# pic_can_relay.net
KiCad netlist of a schematic drawn in EAGLE
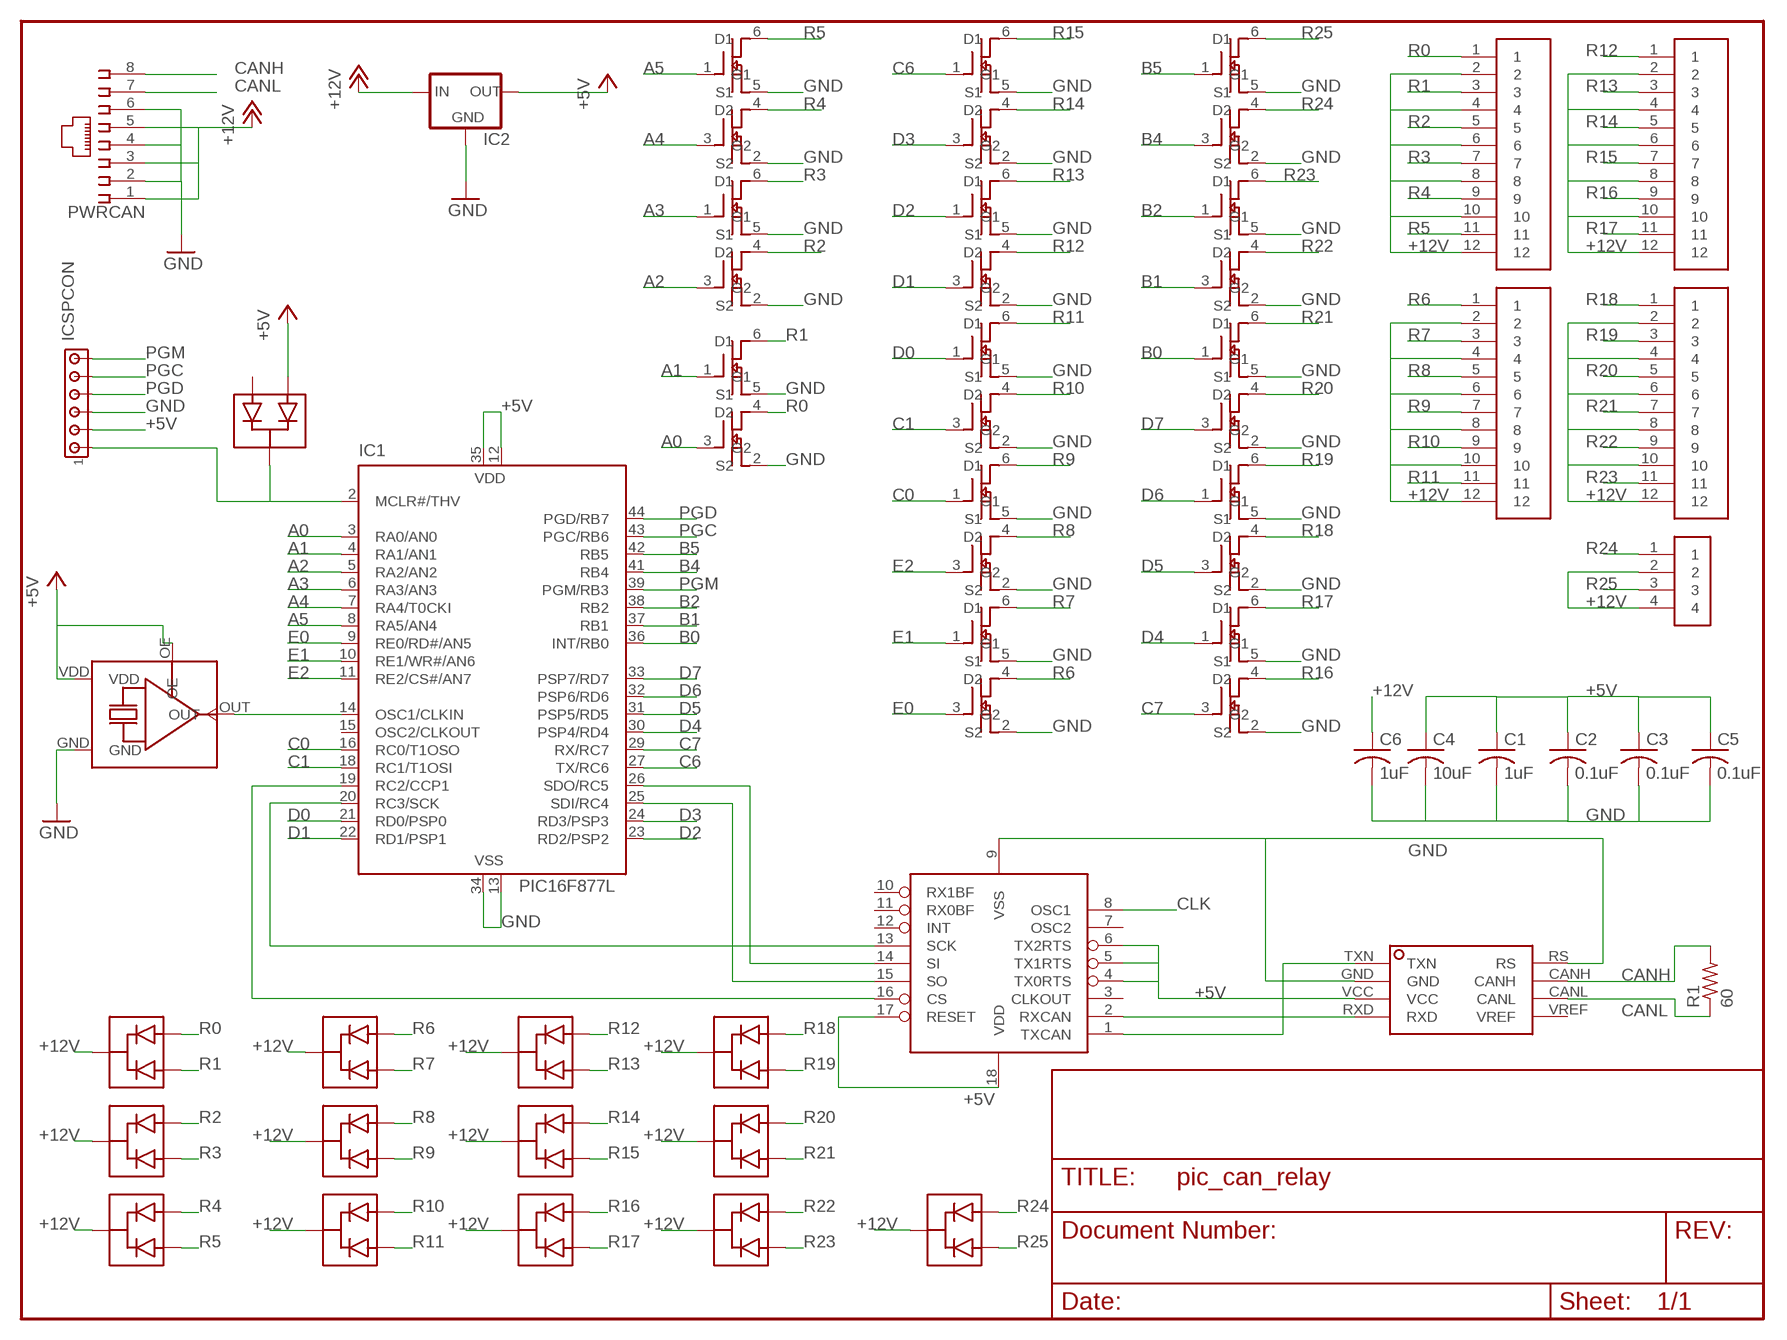
[diagram p0: schematic, sheet 1]

(export (version "E")
  (design (tool "Eeschema 10.0.6"))
  (components
    (comp (ref "C1")
      (value "1uF")
      (footprint "eagle-import:C1206")
      (libsource (lib "eagle-import") (part "C-USC1206"))
    )
    (comp (ref "C2")
      (value "0.1uF")
      (footprint "eagle-import:C0805")
      (libsource (lib "eagle-import") (part "C-USC0805"))
    )
    (comp (ref "C3")
      (value "0.1uF")
      (footprint "eagle-import:C0805")
      (libsource (lib "eagle-import") (part "C-USC0805"))
    )
    (comp (ref "C4")
      (value "10uF")
      (footprint "eagle-import:C1210")
      (libsource (lib "eagle-import") (part "C-USC1210"))
    )
    (comp (ref "C5")
      (value "0.1uF")
      (footprint "eagle-import:C0805")
      (libsource (lib "eagle-import") (part "C-USC0805"))
    )
    (comp (ref "C6")
      (value "1uF")
      (footprint "eagle-import:C1206")
      (libsource (lib "eagle-import") (part "C-USC1206"))
    )
    (comp (ref "D1")
      (value "BAV70_")
      (footprint "eagle-import:SOT-23")
      (libsource (lib "eagle-import") (part "BAV70_"))
    )
    (comp (ref "D2")
      (value "BAV70_")
      (footprint "eagle-import:SOT-23")
      (libsource (lib "eagle-import") (part "BAV70_"))
    )
    (comp (ref "D3")
      (value "BAV70_")
      (footprint "eagle-import:SOT-23")
      (libsource (lib "eagle-import") (part "BAV70_"))
    )
    (comp (ref "D4")
      (value "BAV70_")
      (footprint "eagle-import:SOT-23")
      (libsource (lib "eagle-import") (part "BAV70_"))
    )
    (comp (ref "D5")
      (value "BAV70_")
      (footprint "eagle-import:SOT-23")
      (libsource (lib "eagle-import") (part "BAV70_"))
    )
    (comp (ref "D6")
      (value "BAV70_")
      (footprint "eagle-import:SOT-23")
      (libsource (lib "eagle-import") (part "BAV70_"))
    )
    (comp (ref "D7")
      (value "BAV70_")
      (footprint "eagle-import:SOT-23")
      (libsource (lib "eagle-import") (part "BAV70_"))
    )
    (comp (ref "D8")
      (value "BAV70_")
      (footprint "eagle-import:SOT-23")
      (libsource (lib "eagle-import") (part "BAV70_"))
    )
    (comp (ref "D9")
      (value "BAV70_")
      (footprint "eagle-import:SOT-23")
      (libsource (lib "eagle-import") (part "BAV70_"))
    )
    (comp (ref "D10")
      (value "BAV70_")
      (footprint "eagle-import:SOT-23")
      (libsource (lib "eagle-import") (part "BAV70_"))
    )
    (comp (ref "D11")
      (value "BAV70_")
      (footprint "eagle-import:SOT-23")
      (libsource (lib "eagle-import") (part "BAV70_"))
    )
    (comp (ref "D12")
      (value "BAV70_")
      (footprint "eagle-import:SOT-23")
      (libsource (lib "eagle-import") (part "BAV70_"))
    )
    (comp (ref "D13")
      (value "BAV70_")
      (footprint "eagle-import:SOT-23")
      (libsource (lib "eagle-import") (part "BAV70_"))
    )
    (comp (ref "D14")
      (value "BAV70_")
      (footprint "eagle-import:SOT-23")
      (libsource (lib "eagle-import") (part "BAV70_"))
    )
    (comp (ref "IC1")
      (value "PIC16F877L")
      (footprint "eagle-import:PLCC-44")
      (libsource (lib "eagle-import") (part "PIC16F87L7"))
    )
    (comp (ref "IC2")
      (value "78XXL")
      (footprint "eagle-import:78XXL")
      (libsource (lib "eagle-import") (part "78XXL"))
    )
    (comp (ref "IC3")
      (value "UC5350D")
      (footprint "eagle-import:SOIC8")
      (libsource (lib "eagle-import") (part "UC5350D"))
    )
    (comp (ref "ICSPCON")
      (value "MTA06-100")
      (footprint "eagle-import:10X06MTA")
      (libsource (lib "eagle-import") (part "MTA06-100"))
    )
    (comp (ref "MCP1")
      (value "MCP2510-I/SO")
      (footprint "eagle-import:SO-18W")
      (libsource (lib "eagle-import") (part "MCP2510-I/SO"))
    )
    (comp (ref "PWRCAN")
      (value "555764-1")
      (footprint "eagle-import:555764-1")
      (libsource (lib "eagle-import") (part "555764-1"))
    )
    (comp (ref "R1")
      (value "60")
      (footprint "eagle-import:R0805")
      (libsource (lib "eagle-import") (part "R-US_R0805"))
    )
    (comp (ref "T1")
      (value "NDC7002N\"")
      (footprint "eagle-import:SOT-6")
      (libsource (lib "eagle-import") (part "NDC7002N{dblquote}"))
    )
    (comp (ref "T2")
      (value "NDC7002N\"")
      (footprint "eagle-import:SOT-6")
      (libsource (lib "eagle-import") (part "NDC7002N{dblquote}"))
    )
    (comp (ref "T3")
      (value "NDC7002N\"")
      (footprint "eagle-import:SOT-6")
      (libsource (lib "eagle-import") (part "NDC7002N{dblquote}"))
    )
    (comp (ref "T4")
      (value "NDC7002N\"")
      (footprint "eagle-import:SOT-6")
      (libsource (lib "eagle-import") (part "NDC7002N{dblquote}"))
    )
    (comp (ref "T5")
      (value "NDC7002N\"")
      (footprint "eagle-import:SOT-6")
      (libsource (lib "eagle-import") (part "NDC7002N{dblquote}"))
    )
    (comp (ref "T6")
      (value "NDC7002N\"")
      (footprint "eagle-import:SOT-6")
      (libsource (lib "eagle-import") (part "NDC7002N{dblquote}"))
    )
    (comp (ref "T7")
      (value "NDC7002N\"")
      (footprint "eagle-import:SOT-6")
      (libsource (lib "eagle-import") (part "NDC7002N{dblquote}"))
    )
    (comp (ref "T8")
      (value "NDC7002N\"")
      (footprint "eagle-import:SOT-6")
      (libsource (lib "eagle-import") (part "NDC7002N{dblquote}"))
    )
    (comp (ref "T9")
      (value "NDC7002N\"")
      (footprint "eagle-import:SOT-6")
      (libsource (lib "eagle-import") (part "NDC7002N{dblquote}"))
    )
    (comp (ref "T10")
      (value "NDC7002N\"")
      (footprint "eagle-import:SOT-6")
      (libsource (lib "eagle-import") (part "NDC7002N{dblquote}"))
    )
    (comp (ref "T11")
      (value "NDC7002N\"")
      (footprint "eagle-import:SOT-6")
      (libsource (lib "eagle-import") (part "NDC7002N{dblquote}"))
    )
    (comp (ref "T12")
      (value "NDC7002N\"")
      (footprint "eagle-import:SOT-6")
      (libsource (lib "eagle-import") (part "NDC7002N{dblquote}"))
    )
    (comp (ref "T13")
      (value "NDC7002N\"")
      (footprint "eagle-import:SOT-6")
      (libsource (lib "eagle-import") (part "NDC7002N{dblquote}"))
    )
    (comp (ref "TB1")
      (value "MPT0.5/12-2.54")
      (footprint "eagle-import:MPT0.5_12-2.54")
      (libsource (lib "eagle-import") (part "MPT0.5/12-2.54"))
    )
    (comp (ref "TB2")
      (value "MPT0.5/12-2.54")
      (footprint "eagle-import:MPT0.5_12-2.54")
      (libsource (lib "eagle-import") (part "MPT0.5/12-2.54"))
    )
    (comp (ref "TB3")
      (value "MPT0.5/12-2.54")
      (footprint "eagle-import:MPT0.5_12-2.54")
      (libsource (lib "eagle-import") (part "MPT0.5/12-2.54"))
    )
    (comp (ref "TB4")
      (value "MPT0.5/12-2.54")
      (footprint "eagle-import:MPT0.5_12-2.54")
      (libsource (lib "eagle-import") (part "MPT0.5/12-2.54"))
    )
    (comp (ref "TB5")
      (value "MPT0.5/4-2.54\"")
      (footprint "eagle-import:MPT0.5_4-2.54")
      (libsource (lib "eagle-import") (part "MPT0.5/4-2.54{dblquote}"))
    )
    (comp (ref "U$1")
      (value "SG-615P")
      (footprint "eagle-import:SG-615")
      (libsource (lib "eagle-import") (part "SG-615P"))
    )
  )
  (nets
    (net (code "1") (name "+5V") (class "Default")
      (node (ref "C1") (pin "1") (pinfunction "1_1") (pintype "passive"))
      (node (ref "C2") (pin "1") (pinfunction "1_1") (pintype "passive"))
      (node (ref "C3") (pin "1") (pinfunction "1_1") (pintype "passive"))
      (node (ref "C4") (pin "1") (pinfunction "1_1") (pintype "passive"))
      (node (ref "C5") (pin "1") (pinfunction "1_1") (pintype "passive"))
      (node (ref "D1") (pin "1") (pinfunction "A1_1") (pintype "bidirectional"))
      (node (ref "IC1") (pin "12") (pinfunction "VDD_12") (pintype "power_in"))
      (node (ref "IC1") (pin "35") (pinfunction "VDD_35") (pintype "power_in"))
      (node (ref "IC2") (pin "OUT") (pinfunction "OUT_OUT") (pintype "passive"))
      (node (ref "IC3") (pin "VCC") (pinfunction "VCC_VCC") (pintype "bidirectional"))
      (node (ref "ICSPCON") (pin "5") (pinfunction "2_5") (pintype "passive"))
      (node (ref "MCP1") (pin "17") (pinfunction "RESET_17") (pintype "input"))
      (node (ref "MCP1") (pin "18") (pinfunction "VDD_18") (pintype "power_in"))
      (node (ref "MCP1") (pin "4") (pinfunction "TX0RTS_4") (pintype "input"))
      (node (ref "MCP1") (pin "5") (pinfunction "TX1RTS_5") (pintype "input"))
      (node (ref "MCP1") (pin "6") (pinfunction "TX2RTS_6") (pintype "input"))
      (node (ref "U$1") (pin "OE") (pinfunction "OE_OE") (pintype "input"))
      (node (ref "U$1") (pin "VDD") (pinfunction "VDD_VDD") (pintype "power_in"))
    )
    (net (code "2") (name "+12V") (class "Default")
      (node (ref "C6") (pin "1") (pinfunction "1_1") (pintype "passive"))
      (node (ref "D10") (pin "3") (pinfunction "C_3") (pintype "bidirectional"))
      (node (ref "D11") (pin "3") (pinfunction "C_3") (pintype "bidirectional"))
      (node (ref "D12") (pin "3") (pinfunction "C_3") (pintype "bidirectional"))
      (node (ref "D13") (pin "3") (pinfunction "C_3") (pintype "bidirectional"))
      (node (ref "D14") (pin "3") (pinfunction "C_3") (pintype "bidirectional"))
      (node (ref "D2") (pin "3") (pinfunction "C_3") (pintype "bidirectional"))
      (node (ref "D3") (pin "3") (pinfunction "C_3") (pintype "bidirectional"))
      (node (ref "D4") (pin "3") (pinfunction "C_3") (pintype "bidirectional"))
      (node (ref "D5") (pin "3") (pinfunction "C_3") (pintype "bidirectional"))
      (node (ref "D6") (pin "3") (pinfunction "C_3") (pintype "bidirectional"))
      (node (ref "D7") (pin "3") (pinfunction "C_3") (pintype "bidirectional"))
      (node (ref "D8") (pin "3") (pinfunction "C_3") (pintype "bidirectional"))
      (node (ref "D9") (pin "3") (pinfunction "C_3") (pintype "bidirectional"))
      (node (ref "IC2") (pin "IN") (pinfunction "IN_IN") (pintype "input"))
      (node (ref "PWRCAN") (pin "1") (pinfunction "1_1") (pintype "passive"))
      (node (ref "PWRCAN") (pin "3") (pinfunction "3_3") (pintype "passive"))
      (node (ref "PWRCAN") (pin "5") (pinfunction "5_5") (pintype "passive"))
      (node (ref "TB1") (pin "10") (pinfunction "10_10") (pintype "bidirectional"))
      (node (ref "TB1") (pin "12") (pinfunction "12_12") (pintype "bidirectional"))
      (node (ref "TB1") (pin "2") (pinfunction "2_2") (pintype "bidirectional"))
      (node (ref "TB1") (pin "4") (pinfunction "4_4") (pintype "bidirectional"))
      (node (ref "TB1") (pin "6") (pinfunction "6_6") (pintype "bidirectional"))
      (node (ref "TB1") (pin "8") (pinfunction "8_8") (pintype "bidirectional"))
      (node (ref "TB2") (pin "10") (pinfunction "10_10") (pintype "bidirectional"))
      (node (ref "TB2") (pin "12") (pinfunction "12_12") (pintype "bidirectional"))
      (node (ref "TB2") (pin "2") (pinfunction "2_2") (pintype "bidirectional"))
      (node (ref "TB2") (pin "4") (pinfunction "4_4") (pintype "bidirectional"))
      (node (ref "TB2") (pin "6") (pinfunction "6_6") (pintype "bidirectional"))
      (node (ref "TB2") (pin "8") (pinfunction "8_8") (pintype "bidirectional"))
      (node (ref "TB3") (pin "10") (pinfunction "10_10") (pintype "bidirectional"))
      (node (ref "TB3") (pin "12") (pinfunction "12_12") (pintype "bidirectional"))
      (node (ref "TB3") (pin "2") (pinfunction "2_2") (pintype "bidirectional"))
      (node (ref "TB3") (pin "4") (pinfunction "4_4") (pintype "bidirectional"))
      (node (ref "TB3") (pin "6") (pinfunction "6_6") (pintype "bidirectional"))
      (node (ref "TB3") (pin "8") (pinfunction "8_8") (pintype "bidirectional"))
      (node (ref "TB4") (pin "10") (pinfunction "10_10") (pintype "bidirectional"))
      (node (ref "TB4") (pin "12") (pinfunction "12_12") (pintype "bidirectional"))
      (node (ref "TB4") (pin "2") (pinfunction "2_2") (pintype "bidirectional"))
      (node (ref "TB4") (pin "4") (pinfunction "4_4") (pintype "bidirectional"))
      (node (ref "TB4") (pin "6") (pinfunction "6_6") (pintype "bidirectional"))
      (node (ref "TB4") (pin "8") (pinfunction "8_8") (pintype "bidirectional"))
      (node (ref "TB5") (pin "2") (pinfunction "2_2") (pintype "bidirectional"))
      (node (ref "TB5") (pin "4") (pinfunction "4_4") (pintype "bidirectional"))
    )
    (net (code "3") (name "/A0") (class "Default")
      (node (ref "IC1") (pin "3") (pinfunction "RA0/AN0_3") (pintype "bidirectional"))
      (node (ref "T1") (pin "3") (pinfunction "G2_3") (pintype "bidirectional"))
    )
    (net (code "4") (name "/A1") (class "Default")
      (node (ref "IC1") (pin "4") (pinfunction "RA1/AN1_4") (pintype "bidirectional"))
      (node (ref "T1") (pin "1") (pinfunction "G1_1") (pintype "bidirectional"))
    )
    (net (code "5") (name "/A2") (class "Default")
      (node (ref "IC1") (pin "5") (pinfunction "RA2/AN2_5") (pintype "bidirectional"))
      (node (ref "T2") (pin "3") (pinfunction "G2_3") (pintype "bidirectional"))
    )
    (net (code "6") (name "/A3") (class "Default")
      (node (ref "IC1") (pin "6") (pinfunction "RA3/AN3_6") (pintype "bidirectional"))
      (node (ref "T2") (pin "1") (pinfunction "G1_1") (pintype "bidirectional"))
    )
    (net (code "7") (name "/A4") (class "Default")
      (node (ref "IC1") (pin "7") (pinfunction "RA4/T0CKI_7") (pintype "bidirectional"))
      (node (ref "T3") (pin "3") (pinfunction "G2_3") (pintype "bidirectional"))
    )
    (net (code "8") (name "/A5") (class "Default")
      (node (ref "IC1") (pin "8") (pinfunction "RA5/AN4_8") (pintype "bidirectional"))
      (node (ref "T3") (pin "1") (pinfunction "G1_1") (pintype "bidirectional"))
    )
    (net (code "9") (name "/B0") (class "Default")
      (node (ref "IC1") (pin "36") (pinfunction "INT/RB0_36") (pintype "bidirectional"))
      (node (ref "T11") (pin "1") (pinfunction "G1_1") (pintype "bidirectional"))
    )
    (net (code "10") (name "/B1") (class "Default")
      (node (ref "IC1") (pin "37") (pinfunction "RB1_37") (pintype "bidirectional"))
      (node (ref "T12") (pin "3") (pinfunction "G2_3") (pintype "bidirectional"))
    )
    (net (code "11") (name "/B2") (class "Default")
      (node (ref "IC1") (pin "38") (pinfunction "RB2_38") (pintype "bidirectional"))
      (node (ref "T12") (pin "1") (pinfunction "G1_1") (pintype "bidirectional"))
    )
    (net (code "12") (name "/B4") (class "Default")
      (node (ref "IC1") (pin "41") (pinfunction "RB4_41") (pintype "bidirectional"))
      (node (ref "T13") (pin "3") (pinfunction "G2_3") (pintype "bidirectional"))
    )
    (net (code "13") (name "/B5") (class "Default")
      (node (ref "IC1") (pin "42") (pinfunction "RB5_42") (pintype "bidirectional"))
      (node (ref "T13") (pin "1") (pinfunction "G1_1") (pintype "bidirectional"))
    )
    (net (code "14") (name "/C0") (class "Default")
      (node (ref "IC1") (pin "16") (pinfunction "RC0/T1OSO_16") (pintype "bidirectional"))
      (node (ref "T5") (pin "1") (pinfunction "G1_1") (pintype "bidirectional"))
    )
    (net (code "15") (name "/C1") (class "Default")
      (node (ref "IC1") (pin "18") (pinfunction "RC1/T1OSI_18") (pintype "bidirectional"))
      (node (ref "T6") (pin "3") (pinfunction "G2_3") (pintype "bidirectional"))
    )
    (net (code "16") (name "/C6") (class "Default")
      (node (ref "IC1") (pin "27") (pinfunction "TX/RC6_27") (pintype "bidirectional"))
      (node (ref "T8") (pin "1") (pinfunction "G1_1") (pintype "bidirectional"))
    )
    (net (code "17") (name "/C7") (class "Default")
      (node (ref "IC1") (pin "29") (pinfunction "RX/RC7_29") (pintype "bidirectional"))
      (node (ref "T9") (pin "3") (pinfunction "G2_3") (pintype "bidirectional"))
    )
    (net (code "18") (name "/CANH") (class "Default")
      (node (ref "IC3") (pin "CANH") (pinfunction "CANH_CANH") (pintype "bidirectional"))
      (node (ref "PWRCAN") (pin "8") (pinfunction "8_8") (pintype "passive"))
      (node (ref "R1") (pin "2") (pinfunction "2_2") (pintype "passive"))
    )
    (net (code "19") (name "/CANL") (class "Default")
      (node (ref "IC3") (pin "CANL") (pinfunction "CANL_CANL") (pintype "bidirectional"))
      (node (ref "PWRCAN") (pin "7") (pinfunction "7_7") (pintype "passive"))
      (node (ref "R1") (pin "1") (pinfunction "1_1") (pintype "passive"))
    )
    (net (code "20") (name "/CLK") (class "Default")
      (node (ref "IC1") (pin "14") (pinfunction "OSC1/CLKIN_14") (pintype "input"))
      (node (ref "MCP1") (pin "8") (pinfunction "OSC1_8") (pintype "input"))
      (node (ref "U$1") (pin "OUT") (pinfunction "OUT_OUT") (pintype "bidirectional"))
    )
    (net (code "21") (name "/D0") (class "Default")
      (node (ref "IC1") (pin "21") (pinfunction "RD0/PSP0_21") (pintype "bidirectional"))
      (node (ref "T6") (pin "1") (pinfunction "G1_1") (pintype "bidirectional"))
    )
    (net (code "22") (name "/D1") (class "Default")
      (node (ref "IC1") (pin "22") (pinfunction "RD1/PSP1_22") (pintype "bidirectional"))
      (node (ref "T7") (pin "3") (pinfunction "G2_3") (pintype "bidirectional"))
    )
    (net (code "23") (name "/D2") (class "Default")
      (node (ref "IC1") (pin "23") (pinfunction "RD2/PSP2_23") (pintype "bidirectional"))
      (node (ref "T7") (pin "1") (pinfunction "G1_1") (pintype "bidirectional"))
    )
    (net (code "24") (name "/D3") (class "Default")
      (node (ref "IC1") (pin "24") (pinfunction "RD3/PSP3_24") (pintype "bidirectional"))
      (node (ref "T8") (pin "3") (pinfunction "G2_3") (pintype "bidirectional"))
    )
    (net (code "25") (name "/D4") (class "Default")
      (node (ref "IC1") (pin "30") (pinfunction "PSP4/RD4_30") (pintype "bidirectional"))
      (node (ref "T9") (pin "1") (pinfunction "G1_1") (pintype "bidirectional"))
    )
    (net (code "26") (name "/D5") (class "Default")
      (node (ref "IC1") (pin "31") (pinfunction "PSP5/RD5_31") (pintype "bidirectional"))
      (node (ref "T10") (pin "3") (pinfunction "G2_3") (pintype "bidirectional"))
    )
    (net (code "27") (name "/D6") (class "Default")
      (node (ref "IC1") (pin "32") (pinfunction "PSP6/RD6_32") (pintype "bidirectional"))
      (node (ref "T10") (pin "1") (pinfunction "G1_1") (pintype "bidirectional"))
    )
    (net (code "28") (name "/D7") (class "Default")
      (node (ref "IC1") (pin "33") (pinfunction "PSP7/RD7_33") (pintype "bidirectional"))
      (node (ref "T11") (pin "3") (pinfunction "G2_3") (pintype "bidirectional"))
    )
    (net (code "29") (name "/E0") (class "Default")
      (node (ref "IC1") (pin "9") (pinfunction "RE0/RD#/AN5_9") (pintype "bidirectional"))
      (node (ref "T4") (pin "3") (pinfunction "G2_3") (pintype "bidirectional"))
    )
    (net (code "30") (name "/E1") (class "Default")
      (node (ref "IC1") (pin "10") (pinfunction "RE1/WR#/AN6_10") (pintype "bidirectional"))
      (node (ref "T4") (pin "1") (pinfunction "G1_1") (pintype "bidirectional"))
    )
    (net (code "31") (name "/E2") (class "Default")
      (node (ref "IC1") (pin "11") (pinfunction "RE2/CS#/AN7_11") (pintype "bidirectional"))
      (node (ref "T5") (pin "3") (pinfunction "G2_3") (pintype "bidirectional"))
    )
    (net (code "32") (name "/PGC") (class "Default")
      (node (ref "IC1") (pin "43") (pinfunction "PGC/RB6_43") (pintype "bidirectional"))
      (node (ref "ICSPCON") (pin "2") (pinfunction "5_2") (pintype "passive"))
    )
    (net (code "33") (name "/PGD") (class "Default")
      (node (ref "IC1") (pin "44") (pinfunction "PGD/RB7_44") (pintype "bidirectional"))
      (node (ref "ICSPCON") (pin "3") (pinfunction "4_3") (pintype "passive"))
    )
    (net (code "34") (name "/PGM") (class "Default")
      (node (ref "IC1") (pin "39") (pinfunction "PGM/RB3_39") (pintype "bidirectional"))
      (node (ref "ICSPCON") (pin "1") (pinfunction "6_1") (pintype "passive"))
    )
    (net (code "35") (name "/R0") (class "Default")
      (node (ref "D2") (pin "2") (pinfunction "A2_2") (pintype "bidirectional"))
      (node (ref "T1") (pin "4") (pinfunction "D2_4") (pintype "bidirectional"))
      (node (ref "TB1") (pin "1") (pinfunction "1_1") (pintype "bidirectional"))
    )
    (net (code "36") (name "/R1") (class "Default")
      (node (ref "D2") (pin "1") (pinfunction "A1_1") (pintype "bidirectional"))
      (node (ref "T1") (pin "6") (pinfunction "D1_6") (pintype "bidirectional"))
      (node (ref "TB1") (pin "3") (pinfunction "3_3") (pintype "bidirectional"))
    )
    (net (code "37") (name "/R2") (class "Default")
      (node (ref "D3") (pin "2") (pinfunction "A2_2") (pintype "bidirectional"))
      (node (ref "T2") (pin "4") (pinfunction "D2_4") (pintype "bidirectional"))
      (node (ref "TB1") (pin "5") (pinfunction "5_5") (pintype "bidirectional"))
    )
    (net (code "38") (name "/R3") (class "Default")
      (node (ref "D3") (pin "1") (pinfunction "A1_1") (pintype "bidirectional"))
      (node (ref "T2") (pin "6") (pinfunction "D1_6") (pintype "bidirectional"))
      (node (ref "TB1") (pin "7") (pinfunction "7_7") (pintype "bidirectional"))
    )
    (net (code "39") (name "/R4") (class "Default")
      (node (ref "D4") (pin "2") (pinfunction "A2_2") (pintype "bidirectional"))
      (node (ref "T3") (pin "4") (pinfunction "D2_4") (pintype "bidirectional"))
      (node (ref "TB1") (pin "9") (pinfunction "9_9") (pintype "bidirectional"))
    )
    (net (code "40") (name "/R5") (class "Default")
      (node (ref "D4") (pin "1") (pinfunction "A1_1") (pintype "bidirectional"))
      (node (ref "T3") (pin "6") (pinfunction "D1_6") (pintype "bidirectional"))
      (node (ref "TB1") (pin "11") (pinfunction "11_11") (pintype "bidirectional"))
    )
    (net (code "41") (name "/R6") (class "Default")
      (node (ref "D5") (pin "2") (pinfunction "A2_2") (pintype "bidirectional"))
      (node (ref "T4") (pin "4") (pinfunction "D2_4") (pintype "bidirectional"))
      (node (ref "TB2") (pin "1") (pinfunction "1_1") (pintype "bidirectional"))
    )
    (net (code "42") (name "/R7") (class "Default")
      (node (ref "D5") (pin "1") (pinfunction "A1_1") (pintype "bidirectional"))
      (node (ref "T4") (pin "6") (pinfunction "D1_6") (pintype "bidirectional"))
      (node (ref "TB2") (pin "3") (pinfunction "3_3") (pintype "bidirectional"))
    )
    (net (code "43") (name "/R8") (class "Default")
      (node (ref "D6") (pin "2") (pinfunction "A2_2") (pintype "bidirectional"))
      (node (ref "T5") (pin "4") (pinfunction "D2_4") (pintype "bidirectional"))
      (node (ref "TB2") (pin "5") (pinfunction "5_5") (pintype "bidirectional"))
    )
    (net (code "44") (name "/R9") (class "Default")
      (node (ref "D6") (pin "1") (pinfunction "A1_1") (pintype "bidirectional"))
      (node (ref "T5") (pin "6") (pinfunction "D1_6") (pintype "bidirectional"))
      (node (ref "TB2") (pin "7") (pinfunction "7_7") (pintype "bidirectional"))
    )
    (net (code "45") (name "/R10") (class "Default")
      (node (ref "D7") (pin "2") (pinfunction "A2_2") (pintype "bidirectional"))
      (node (ref "T6") (pin "4") (pinfunction "D2_4") (pintype "bidirectional"))
      (node (ref "TB2") (pin "9") (pinfunction "9_9") (pintype "bidirectional"))
    )
    (net (code "46") (name "/R11") (class "Default")
      (node (ref "D7") (pin "1") (pinfunction "A1_1") (pintype "bidirectional"))
      (node (ref "T6") (pin "6") (pinfunction "D1_6") (pintype "bidirectional"))
      (node (ref "TB2") (pin "11") (pinfunction "11_11") (pintype "bidirectional"))
    )
    (net (code "47") (name "/R12") (class "Default")
      (node (ref "D8") (pin "2") (pinfunction "A2_2") (pintype "bidirectional"))
      (node (ref "T7") (pin "4") (pinfunction "D2_4") (pintype "bidirectional"))
      (node (ref "TB3") (pin "1") (pinfunction "1_1") (pintype "bidirectional"))
    )
    (net (code "48") (name "/R13") (class "Default")
      (node (ref "D8") (pin "1") (pinfunction "A1_1") (pintype "bidirectional"))
      (node (ref "T7") (pin "6") (pinfunction "D1_6") (pintype "bidirectional"))
      (node (ref "TB3") (pin "3") (pinfunction "3_3") (pintype "bidirectional"))
    )
    (net (code "49") (name "/R14") (class "Default")
      (node (ref "D9") (pin "2") (pinfunction "A2_2") (pintype "bidirectional"))
      (node (ref "T8") (pin "4") (pinfunction "D2_4") (pintype "bidirectional"))
      (node (ref "TB3") (pin "5") (pinfunction "5_5") (pintype "bidirectional"))
    )
    (net (code "50") (name "/R15") (class "Default")
      (node (ref "D9") (pin "1") (pinfunction "A1_1") (pintype "bidirectional"))
      (node (ref "T8") (pin "6") (pinfunction "D1_6") (pintype "bidirectional"))
      (node (ref "TB3") (pin "7") (pinfunction "7_7") (pintype "bidirectional"))
    )
    (net (code "51") (name "/R16") (class "Default")
      (node (ref "D10") (pin "2") (pinfunction "A2_2") (pintype "bidirectional"))
      (node (ref "T9") (pin "4") (pinfunction "D2_4") (pintype "bidirectional"))
      (node (ref "TB3") (pin "9") (pinfunction "9_9") (pintype "bidirectional"))
    )
    (net (code "52") (name "/R17") (class "Default")
      (node (ref "D10") (pin "1") (pinfunction "A1_1") (pintype "bidirectional"))
      (node (ref "T9") (pin "6") (pinfunction "D1_6") (pintype "bidirectional"))
      (node (ref "TB3") (pin "11") (pinfunction "11_11") (pintype "bidirectional"))
    )
    (net (code "53") (name "/R18") (class "Default")
      (node (ref "D11") (pin "2") (pinfunction "A2_2") (pintype "bidirectional"))
      (node (ref "T10") (pin "4") (pinfunction "D2_4") (pintype "bidirectional"))
      (node (ref "TB4") (pin "1") (pinfunction "1_1") (pintype "bidirectional"))
    )
    (net (code "54") (name "/R19") (class "Default")
      (node (ref "D11") (pin "1") (pinfunction "A1_1") (pintype "bidirectional"))
      (node (ref "T10") (pin "6") (pinfunction "D1_6") (pintype "bidirectional"))
      (node (ref "TB4") (pin "3") (pinfunction "3_3") (pintype "bidirectional"))
    )
    (net (code "55") (name "/R20") (class "Default")
      (node (ref "D12") (pin "2") (pinfunction "A2_2") (pintype "bidirectional"))
      (node (ref "T11") (pin "4") (pinfunction "D2_4") (pintype "bidirectional"))
      (node (ref "TB4") (pin "5") (pinfunction "5_5") (pintype "bidirectional"))
    )
    (net (code "56") (name "/R21") (class "Default")
      (node (ref "D12") (pin "1") (pinfunction "A1_1") (pintype "bidirectional"))
      (node (ref "T11") (pin "6") (pinfunction "D1_6") (pintype "bidirectional"))
      (node (ref "TB4") (pin "7") (pinfunction "7_7") (pintype "bidirectional"))
    )
    (net (code "57") (name "/R22") (class "Default")
      (node (ref "D13") (pin "2") (pinfunction "A2_2") (pintype "bidirectional"))
      (node (ref "T12") (pin "4") (pinfunction "D2_4") (pintype "bidirectional"))
      (node (ref "TB4") (pin "9") (pinfunction "9_9") (pintype "bidirectional"))
    )
    (net (code "58") (name "/R23") (class "Default")
      (node (ref "D13") (pin "1") (pinfunction "A1_1") (pintype "bidirectional"))
      (node (ref "T12") (pin "6") (pinfunction "D1_6") (pintype "bidirectional"))
      (node (ref "TB4") (pin "11") (pinfunction "11_11") (pintype "bidirectional"))
    )
    (net (code "59") (name "/R24") (class "Default")
      (node (ref "D14") (pin "2") (pinfunction "A2_2") (pintype "bidirectional"))
      (node (ref "T13") (pin "4") (pinfunction "D2_4") (pintype "bidirectional"))
      (node (ref "TB5") (pin "1") (pinfunction "1_1") (pintype "bidirectional"))
    )
    (net (code "60") (name "/R25") (class "Default")
      (node (ref "D14") (pin "1") (pinfunction "A1_1") (pintype "bidirectional"))
      (node (ref "T13") (pin "6") (pinfunction "D1_6") (pintype "bidirectional"))
      (node (ref "TB5") (pin "3") (pinfunction "3_3") (pintype "bidirectional"))
    )
    (net (code "61") (name "GND") (class "Default")
      (node (ref "C1") (pin "2") (pinfunction "2_2") (pintype "passive"))
      (node (ref "C2") (pin "2") (pinfunction "2_2") (pintype "passive"))
      (node (ref "C3") (pin "2") (pinfunction "2_2") (pintype "passive"))
      (node (ref "C4") (pin "2") (pinfunction "2_2") (pintype "passive"))
      (node (ref "C5") (pin "2") (pinfunction "2_2") (pintype "passive"))
      (node (ref "C6") (pin "2") (pinfunction "2_2") (pintype "passive"))
      (node (ref "IC1") (pin "13") (pinfunction "VSS_13") (pintype "power_in"))
      (node (ref "IC1") (pin "34") (pinfunction "VSS_34") (pintype "power_in"))
      (node (ref "IC2") (pin "GND") (pinfunction "GND_GND") (pintype "input"))
      (node (ref "IC3") (pin "GND") (pinfunction "GND_GND") (pintype "bidirectional"))
      (node (ref "IC3") (pin "RS") (pinfunction "RS_RS") (pintype "bidirectional"))
      (node (ref "ICSPCON") (pin "4") (pinfunction "3_4") (pintype "passive"))
      (node (ref "MCP1") (pin "9") (pinfunction "VSS_9") (pintype "power_in"))
      (node (ref "PWRCAN") (pin "2") (pinfunction "2_2") (pintype "passive"))
      (node (ref "PWRCAN") (pin "4") (pinfunction "4_4") (pintype "passive"))
      (node (ref "PWRCAN") (pin "6") (pinfunction "6_6") (pintype "passive"))
      (node (ref "T1") (pin "2") (pinfunction "S2_2") (pintype "bidirectional"))
      (node (ref "T1") (pin "5") (pinfunction "S1_5") (pintype "bidirectional"))
      (node (ref "T10") (pin "2") (pinfunction "S2_2") (pintype "bidirectional"))
      (node (ref "T10") (pin "5") (pinfunction "S1_5") (pintype "bidirectional"))
      (node (ref "T11") (pin "2") (pinfunction "S2_2") (pintype "bidirectional"))
      (node (ref "T11") (pin "5") (pinfunction "S1_5") (pintype "bidirectional"))
      (node (ref "T12") (pin "2") (pinfunction "S2_2") (pintype "bidirectional"))
      (node (ref "T12") (pin "5") (pinfunction "S1_5") (pintype "bidirectional"))
      (node (ref "T13") (pin "2") (pinfunction "S2_2") (pintype "bidirectional"))
      (node (ref "T13") (pin "5") (pinfunction "S1_5") (pintype "bidirectional"))
      (node (ref "T2") (pin "2") (pinfunction "S2_2") (pintype "bidirectional"))
      (node (ref "T2") (pin "5") (pinfunction "S1_5") (pintype "bidirectional"))
      (node (ref "T3") (pin "2") (pinfunction "S2_2") (pintype "bidirectional"))
      (node (ref "T3") (pin "5") (pinfunction "S1_5") (pintype "bidirectional"))
      (node (ref "T4") (pin "2") (pinfunction "S2_2") (pintype "bidirectional"))
      (node (ref "T4") (pin "5") (pinfunction "S1_5") (pintype "bidirectional"))
      (node (ref "T5") (pin "2") (pinfunction "S2_2") (pintype "bidirectional"))
      (node (ref "T5") (pin "5") (pinfunction "S1_5") (pintype "bidirectional"))
      (node (ref "T6") (pin "2") (pinfunction "S2_2") (pintype "bidirectional"))
      (node (ref "T6") (pin "5") (pinfunction "S1_5") (pintype "bidirectional"))
      (node (ref "T7") (pin "2") (pinfunction "S2_2") (pintype "bidirectional"))
      (node (ref "T7") (pin "5") (pinfunction "S1_5") (pintype "bidirectional"))
      (node (ref "T8") (pin "2") (pinfunction "S2_2") (pintype "bidirectional"))
      (node (ref "T8") (pin "5") (pinfunction "S1_5") (pintype "bidirectional"))
      (node (ref "T9") (pin "2") (pinfunction "S2_2") (pintype "bidirectional"))
      (node (ref "T9") (pin "5") (pinfunction "S1_5") (pintype "bidirectional"))
      (node (ref "U$1") (pin "GND") (pinfunction "GND_GND") (pintype "power_in"))
    )
    (net (code "62") (name "Net-(D1-C)") (class "Default")
      (node (ref "D1") (pin "3") (pinfunction "C_3") (pintype "bidirectional"))
      (node (ref "IC1") (pin "2") (pinfunction "MCLR#/THV_2") (pintype "input"))
      (node (ref "ICSPCON") (pin "6") (pinfunction "1_6") (pintype "passive"))
    )
    (net (code "63") (name "Net-(IC1-RC2{slash}CCP1)") (class "Default")
      (node (ref "IC1") (pin "19") (pinfunction "RC2/CCP1_19") (pintype "bidirectional"))
      (node (ref "MCP1") (pin "16") (pinfunction "CS_16") (pintype "input"))
    )
    (net (code "64") (name "Net-(IC1-RC3{slash}SCK)") (class "Default")
      (node (ref "IC1") (pin "20") (pinfunction "RC3/SCK_20") (pintype "bidirectional"))
      (node (ref "MCP1") (pin "13") (pinfunction "SCK_13") (pintype "input"))
    )
    (net (code "65") (name "Net-(IC1-SDI{slash}RC4)") (class "Default")
      (node (ref "IC1") (pin "25") (pinfunction "SDI/RC4_25") (pintype "bidirectional"))
      (node (ref "MCP1") (pin "15") (pinfunction "SO_15") (pintype "output"))
    )
    (net (code "66") (name "Net-(IC1-SDO{slash}RC5)") (class "Default")
      (node (ref "IC1") (pin "26") (pinfunction "SDO/RC5_26") (pintype "bidirectional"))
      (node (ref "MCP1") (pin "14") (pinfunction "SI_14") (pintype "input"))
    )
    (net (code "67") (name "Net-(MCP1-RXCAN)") (class "Default")
      (node (ref "IC3") (pin "RXD") (pinfunction "RXD_RXD") (pintype "bidirectional"))
      (node (ref "MCP1") (pin "2") (pinfunction "RXCAN_2") (pintype "input"))
    )
    (net (code "68") (name "Net-(MCP1-TXCAN)") (class "Default")
      (node (ref "IC3") (pin "TXN") (pinfunction "TXN_TXN") (pintype "bidirectional"))
      (node (ref "MCP1") (pin "1") (pinfunction "TXCAN_1") (pintype "output"))
    )
    (net (code "69") (name "unconnected-(D1-A2-Pad2)") (class "Default")
      (node (ref "D1") (pin "2") (pinfunction "A2_2") (pintype "bidirectional"))
    )
    (net (code "70") (name "unconnected-(IC1-OSC2{slash}CLKOUT-Pad15)") (class "Default")
      (node (ref "IC1") (pin "15") (pinfunction "OSC2/CLKOUT_15") (pintype "output"))
    )
    (net (code "71") (name "unconnected-(IC3-PadVREF)") (class "Default")
      (node (ref "IC3") (pin "VREF") (pinfunction "VREF_VREF") (pintype "bidirectional"))
    )
    (net (code "72") (name "unconnected-(MCP1-CLKOUT-Pad3)") (class "Default")
      (node (ref "MCP1") (pin "3") (pinfunction "CLKOUT_3") (pintype "output"))
    )
    (net (code "73") (name "unconnected-(MCP1-INT-Pad12)") (class "Default")
      (node (ref "MCP1") (pin "12") (pinfunction "INT_12") (pintype "output"))
    )
    (net (code "74") (name "unconnected-(MCP1-OSC2-Pad7)") (class "Default")
      (node (ref "MCP1") (pin "7") (pinfunction "OSC2_7") (pintype "output"))
    )
    (net (code "75") (name "unconnected-(MCP1-RX0BF-Pad11)") (class "Default")
      (node (ref "MCP1") (pin "11") (pinfunction "RX0BF_11") (pintype "output"))
    )
    (net (code "76") (name "unconnected-(MCP1-RX1BF-Pad10)") (class "Default")
      (node (ref "MCP1") (pin "10") (pinfunction "RX1BF_10") (pintype "output"))
    )
  )
)
